# v5.net
KiCad netlist of a schematic drawn in EAGLE
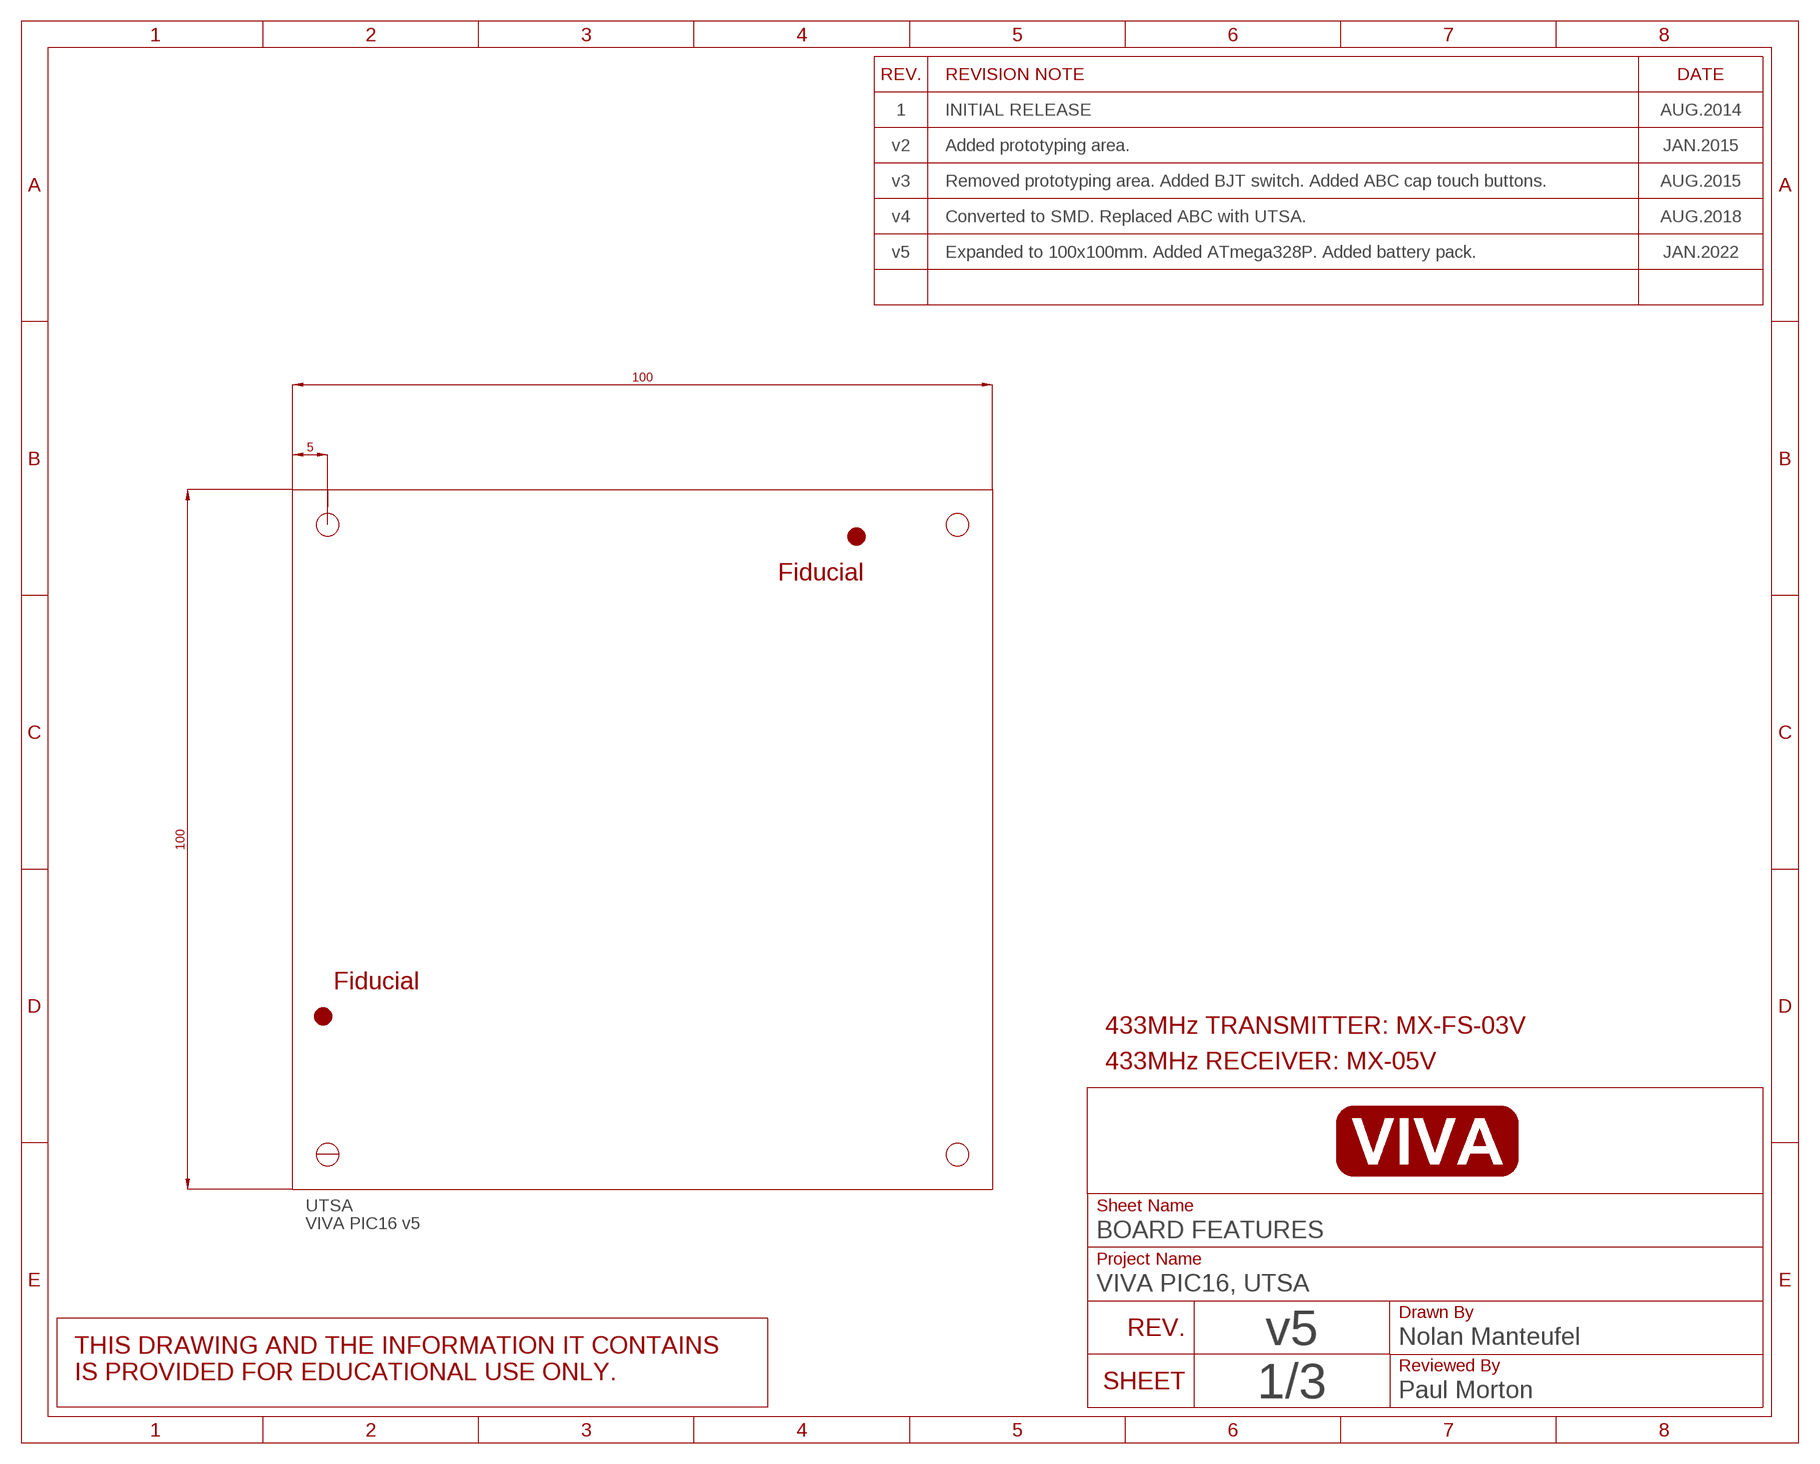
[diagram p0: schematic, sheet 1]
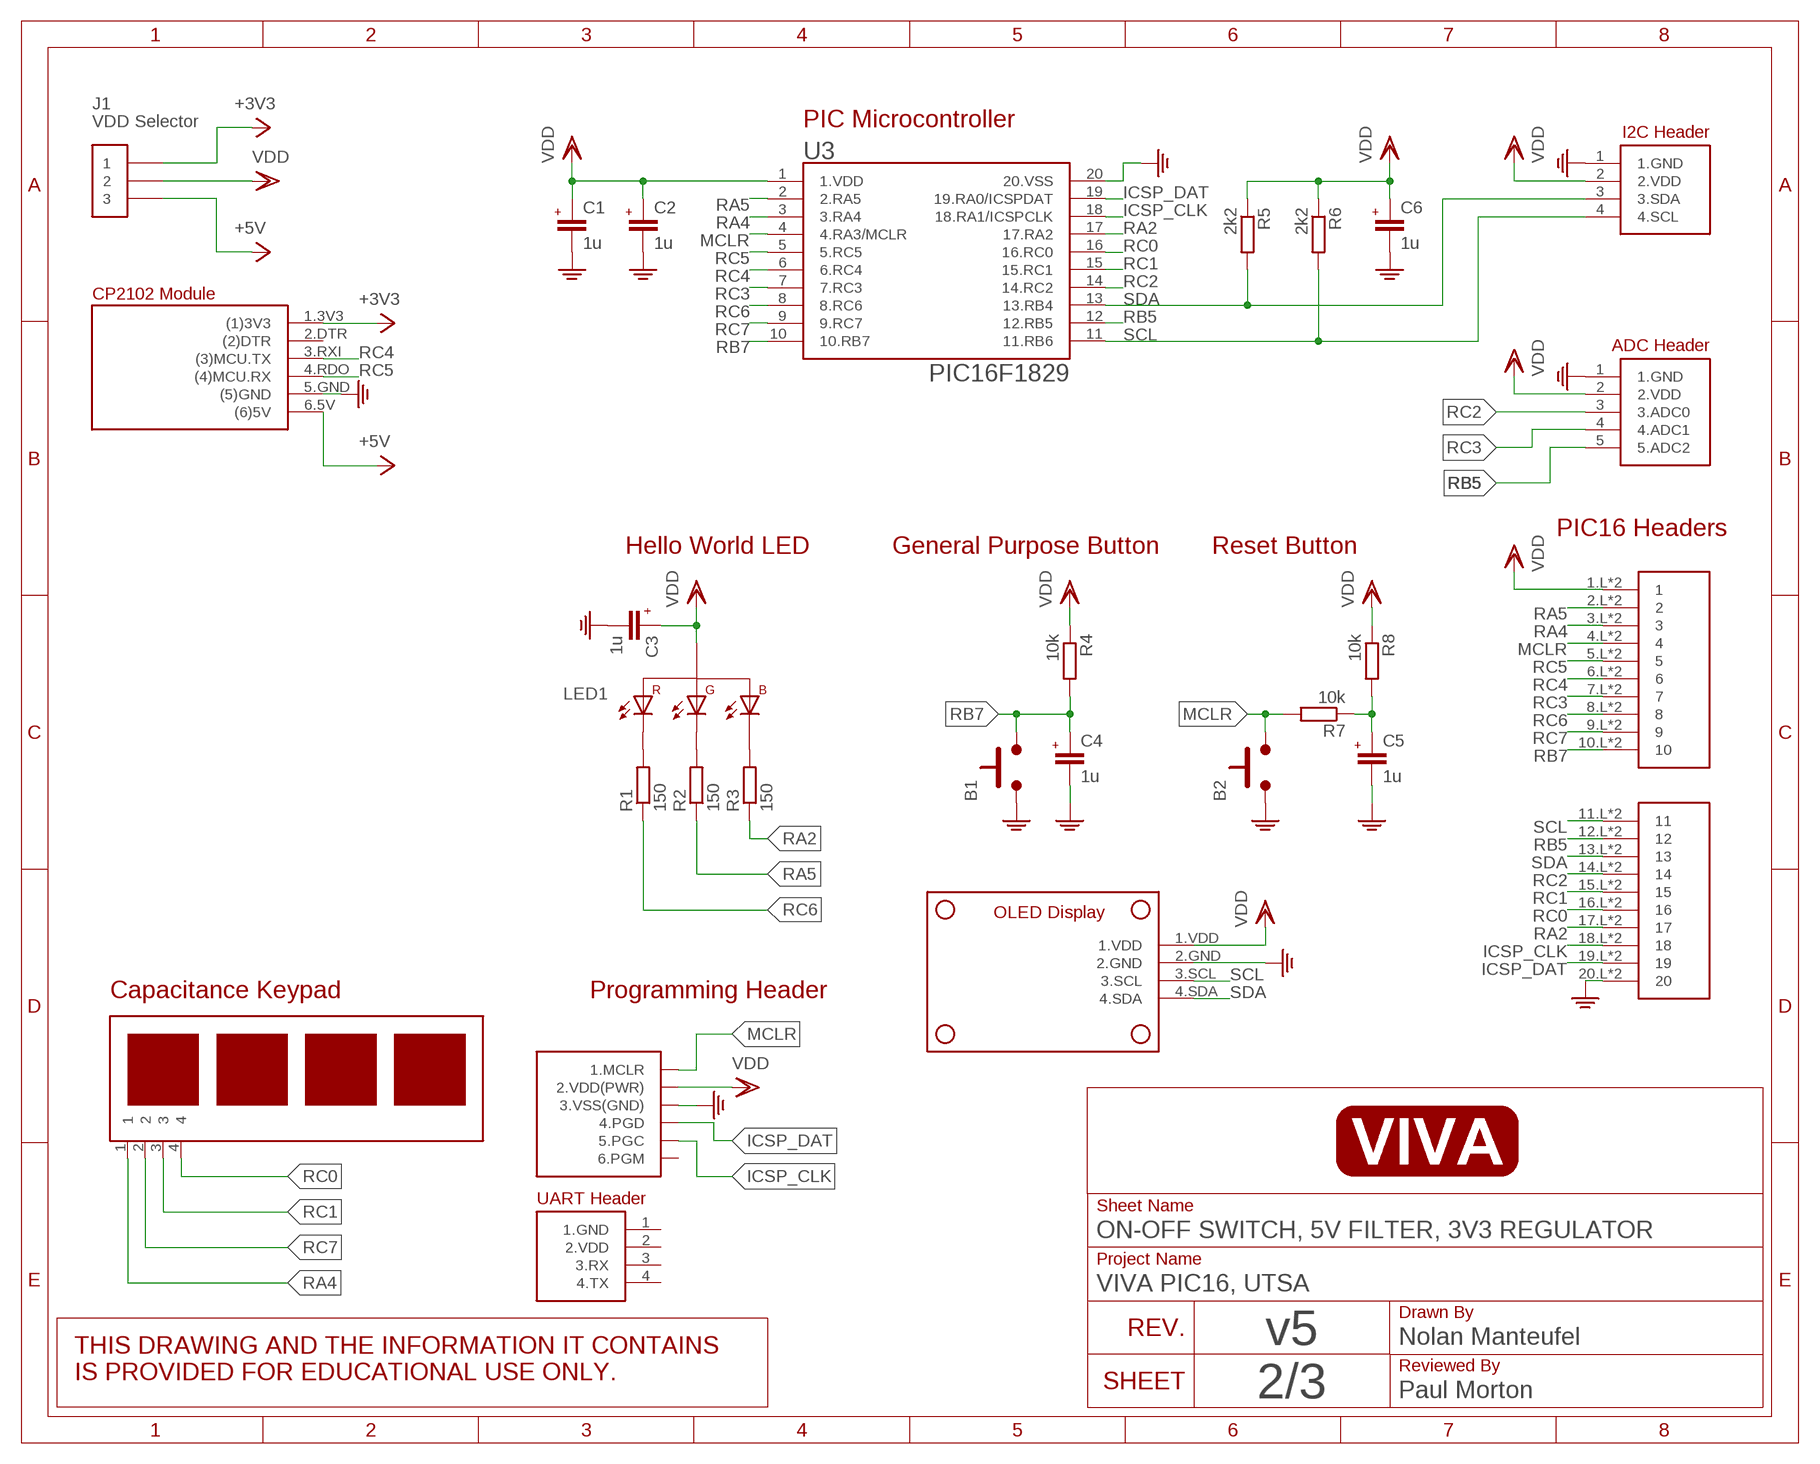
[diagram p1: schematic, sheet 2]
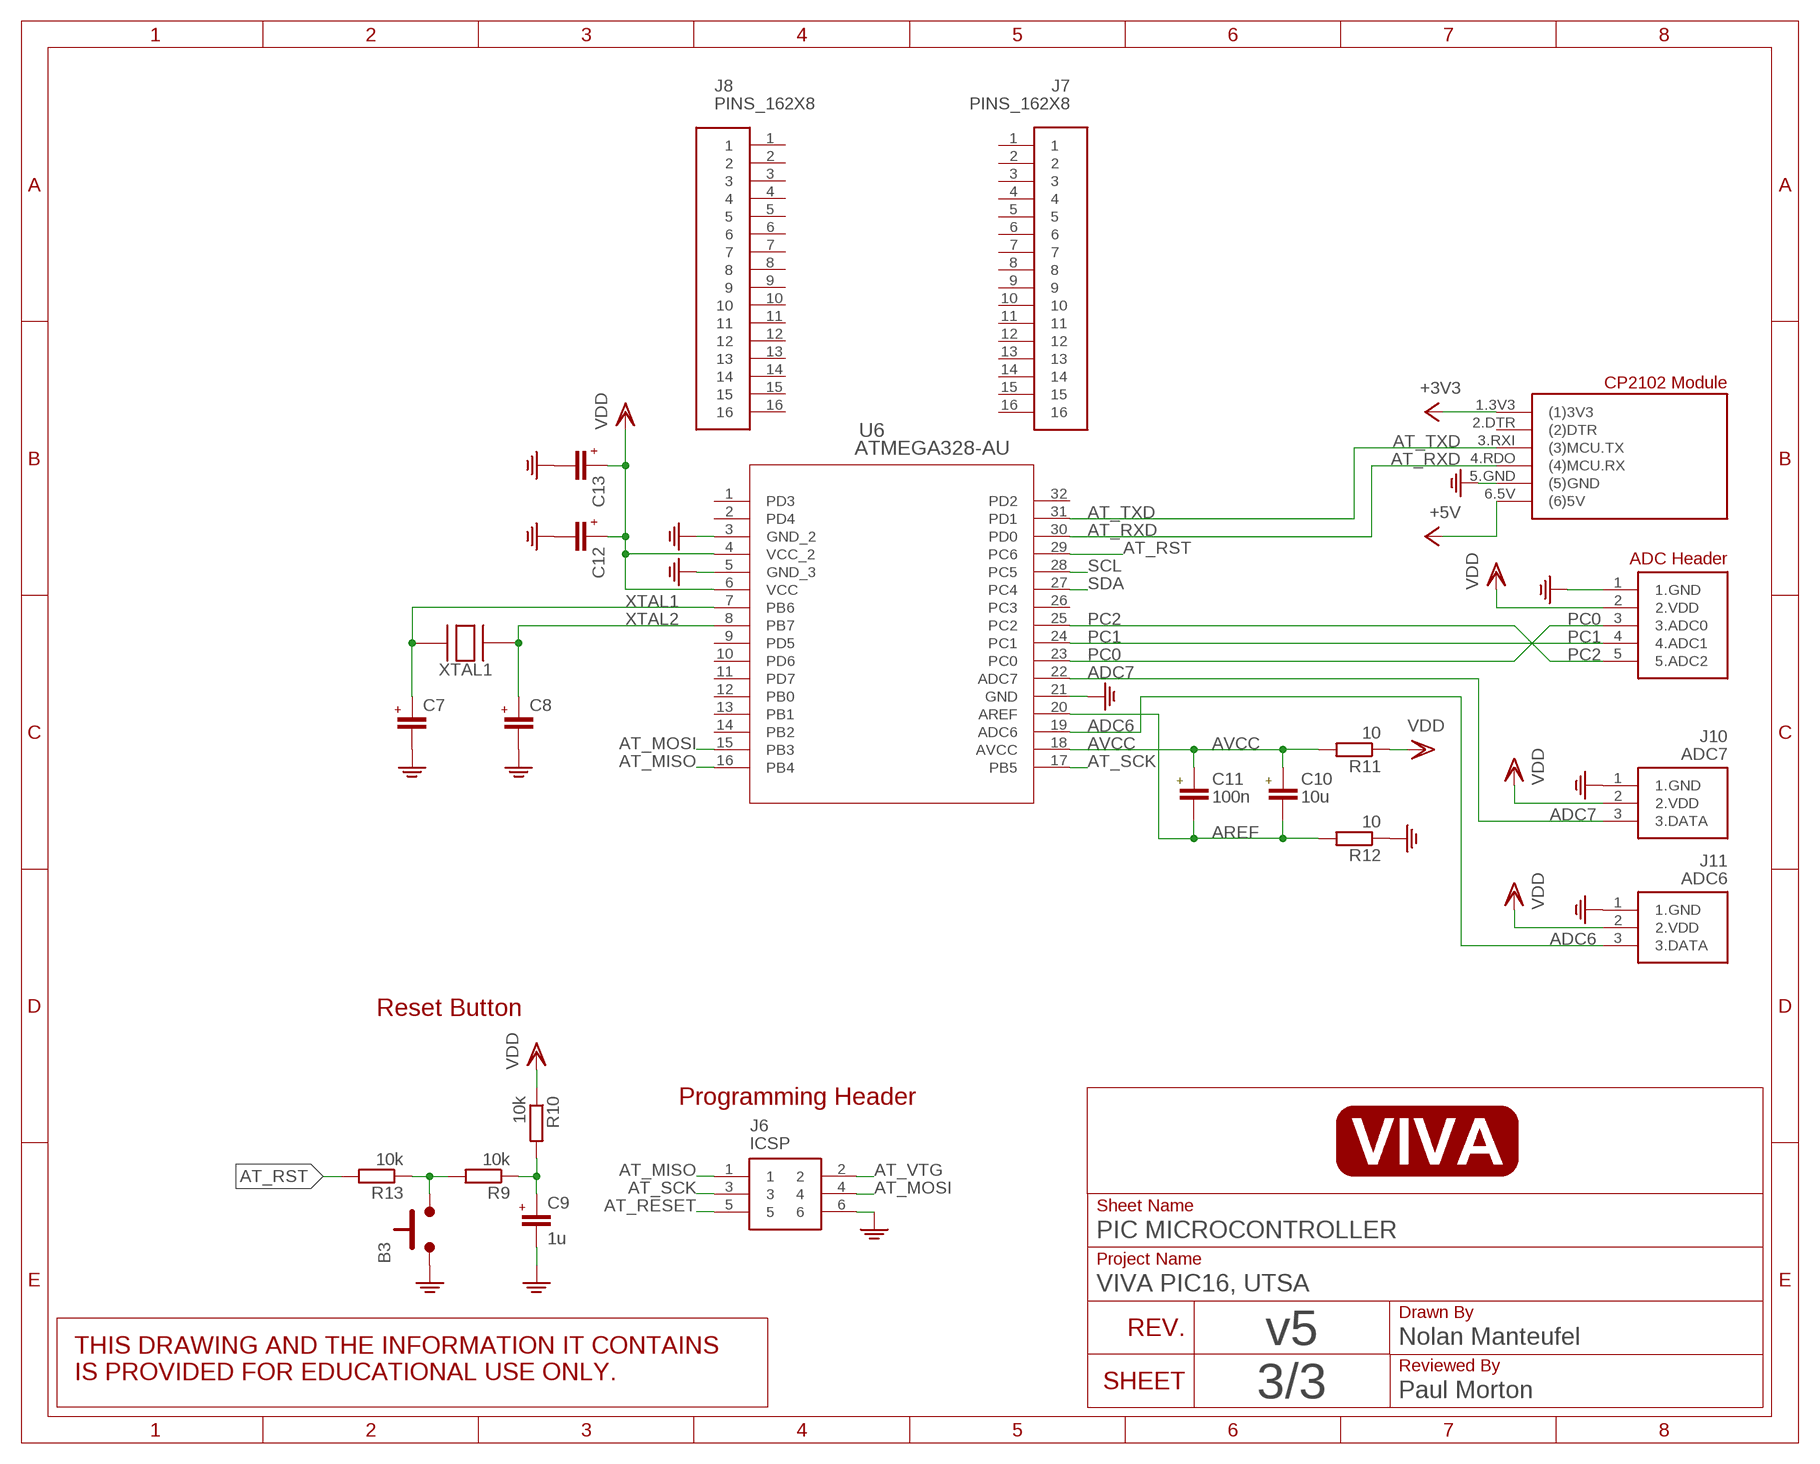
[diagram p2: schematic, sheet 3]

(export (version "E")
  (design (tool "Eeschema 10.0.6"))
  (components
    (comp (ref "B3")
      (value "PUSHBUTTON6X6MM")
      (footprint "eagle-import:6X6MM")
      (libsource (lib "eagle-import") (part "PUSHBUTTON6X6MM"))
    )
    (comp (ref "C7")
      (value "C0805")
      (footprint "eagle-import:C0805")
      (libsource (lib "eagle-import") (part "C0805"))
    )
    (comp (ref "C8")
      (value "C0805")
      (footprint "eagle-import:C0805")
      (libsource (lib "eagle-import") (part "C0805"))
    )
    (comp (ref "C9")
      (value "1u")
      (footprint "eagle-import:C0805")
      (libsource (lib "eagle-import") (part "C0805"))
    )
    (comp (ref "C10")
      (value "10u")
      (footprint "eagle-import:C0805")
      (libsource (lib "eagle-import") (part "C-EU_C0805"))
    )
    (comp (ref "C11")
      (value "100n")
      (footprint "eagle-import:C0805")
      (libsource (lib "eagle-import") (part "C-EU_C0805"))
    )
    (comp (ref "C12")
      (value "C0805")
      (footprint "eagle-import:C0805")
      (libsource (lib "eagle-import") (part "C0805"))
    )
    (comp (ref "C13")
      (value "C0805")
      (footprint "eagle-import:C0805")
      (libsource (lib "eagle-import") (part "C0805"))
    )
    (comp (ref "J6")
      (value "ICSP")
      (footprint "eagle-import:PINS_6-2X3")
      (libsource (lib "eagle-import") (part "PINS_6-2X3"))
    )
    (comp (ref "J7")
      (value "PINS_162X8")
      (footprint "eagle-import:PINS16_2X8")
      (libsource (lib "eagle-import") (part "PINS_162X8"))
    )
    (comp (ref "J8")
      (value "PINS_162X8")
      (footprint "eagle-import:PINS16_2X8")
      (libsource (lib "eagle-import") (part "PINS_162X8"))
    )
    (comp (ref "J9")
      (value "VIVA-HEADER-ADC-PIC16")
      (footprint "eagle-import:VIVA-HEADER-ADC-PIC16")
      (libsource (lib "eagle-import") (part "VIVA-HEADER-ADC-PIC16"))
    )
    (comp (ref "J10")
      (value "ADC7")
      (footprint "eagle-import:VIVA-HEADER-GPIO-RA-1")
      (libsource (lib "eagle-import") (part "VIVA-HEADER-GPIO-1"))
    )
    (comp (ref "J11")
      (value "ADC6")
      (footprint "eagle-import:VIVA-HEADER-GPIO-RA-1")
      (libsource (lib "eagle-import") (part "VIVA-HEADER-GPIO-1"))
    )
    (comp (ref "R9")
      (value "10k")
      (footprint "eagle-import:R0805")
      (libsource (lib "eagle-import") (part "R-EU__R0805"))
    )
    (comp (ref "R10")
      (value "10k")
      (footprint "eagle-import:R0805")
      (libsource (lib "eagle-import") (part "R-EU__R0805"))
    )
    (comp (ref "R11")
      (value "10")
      (footprint "eagle-import:R0805")
      (libsource (lib "eagle-import") (part "R-EU__R0805"))
    )
    (comp (ref "R12")
      (value "10")
      (footprint "eagle-import:R0805")
      (libsource (lib "eagle-import") (part "R-EU__R0805"))
    )
    (comp (ref "R13")
      (value "10k")
      (footprint "eagle-import:R0805")
      (libsource (lib "eagle-import") (part "R-EU__R0805"))
    )
    (comp (ref "U6")
      (value "ATMEGA328-AU")
      (footprint "eagle-import:32A_ATM")
      (fields (field (name "COPYRIGHT") "Copyright (C) 2021 Ultra Librarian. All rights reserved."))
      (libsource (lib "eagle-import") (part "ATMEGA328-AU"))
    )
    (comp (ref "U7")
      (value "VIVA_USB-TTL")
      (footprint "eagle-import:VIVA_USB_TTL_SUBTEXT")
      (libsource (lib "eagle-import") (part "VIVA_USB-TTL"))
    )
    (comp (ref "XTAL1")
      (value "CRYSTAL-SMD")
      (footprint "eagle-import:HC49S-SMD")
      (libsource (lib "eagle-import") (part "CRYSTAL-SMD"))
    )
    (comp (ref "B1")
      (value "PUSHBUTTON6X6MM")
      (footprint "eagle-import:6X6MM")
      (libsource (lib "eagle-import") (part "PUSHBUTTON6X6MM"))
    )
    (comp (ref "B2")
      (value "PUSHBUTTON6X6MM")
      (footprint "eagle-import:6X6MM")
      (libsource (lib "eagle-import") (part "PUSHBUTTON6X6MM"))
    )
    (comp (ref "C1")
      (value "1u")
      (footprint "eagle-import:C0805")
      (libsource (lib "eagle-import") (part "C0805"))
    )
    (comp (ref "C2")
      (value "1u")
      (footprint "eagle-import:C0805")
      (libsource (lib "eagle-import") (part "C0805"))
    )
    (comp (ref "C3")
      (value "1u")
      (footprint "eagle-import:C0805")
      (libsource (lib "eagle-import") (part "C0805"))
    )
    (comp (ref "C4")
      (value "1u")
      (footprint "eagle-import:C0805")
      (libsource (lib "eagle-import") (part "C0805"))
    )
    (comp (ref "C5")
      (value "1u")
      (footprint "eagle-import:C0805")
      (libsource (lib "eagle-import") (part "C0805"))
    )
    (comp (ref "C6")
      (value "1u")
      (footprint "eagle-import:C0805")
      (libsource (lib "eagle-import") (part "C0805"))
    )
    (comp (ref "J1")
      (value "VDD Selector")
      (footprint "eagle-import:PINS_3")
      (libsource (lib "eagle-import") (part "PINS_3_2.54"))
    )
    (comp (ref "J4")
      (value "PICKIT3")
      (footprint "eagle-import:PICKIT3")
      (libsource (lib "eagle-import") (part "PICKIT3"))
    )
    (comp (ref "J5")
      (value "VIVA-HEADER-ADC-PIC16")
      (footprint "eagle-import:VIVA-HEADER-ADC-PIC16")
      (libsource (lib "eagle-import") (part "VIVA-HEADER-ADC-PIC16"))
    )
    (comp (ref "LED1")
      (value "LED_RGBLTST-C19FD1WT")
      (footprint "eagle-import:0805_RGB")
      (libsource (lib "eagle-import") (part "LED_RGBLTST-C19FD1WT"))
    )
    (comp (ref "R1")
      (value "150")
      (footprint "eagle-import:R0805")
      (libsource (lib "eagle-import") (part "R-EU__R0805"))
    )
    (comp (ref "R2")
      (value "150")
      (footprint "eagle-import:R0805")
      (libsource (lib "eagle-import") (part "R-EU__R0805"))
    )
    (comp (ref "R3")
      (value "150")
      (footprint "eagle-import:R0805")
      (libsource (lib "eagle-import") (part "R-EU__R0805"))
    )
    (comp (ref "R4")
      (value "10k")
      (footprint "eagle-import:R0805")
      (libsource (lib "eagle-import") (part "R-EU__R0805"))
    )
    (comp (ref "R5")
      (value "2k2")
      (footprint "eagle-import:R0805")
      (libsource (lib "eagle-import") (part "R-EU__R0805"))
    )
    (comp (ref "R6")
      (value "2k2")
      (footprint "eagle-import:R0805")
      (libsource (lib "eagle-import") (part "R-EU__R0805"))
    )
    (comp (ref "R7")
      (value "10k")
      (footprint "eagle-import:R0805")
      (libsource (lib "eagle-import") (part "R-EU__R0805"))
    )
    (comp (ref "R8")
      (value "10k")
      (footprint "eagle-import:R0805")
      (libsource (lib "eagle-import") (part "R-EU__R0805"))
    )
    (comp (ref "U$2")
      (value "VIVA-HEADER-UART-XS")
      (footprint "eagle-import:PINS_4")
      (libsource (lib "eagle-import") (part "VIVA-HEADER-UART-XS"))
    )
    (comp (ref "U$3")
      (value "VIVA_OLED")
      (footprint "eagle-import:VIVA_OLED-I2C")
      (libsource (lib "eagle-import") (part "VIVA_OLED"))
    )
    (comp (ref "U1")
      (value "VIVA_UTSA-KEYPADV5")
      (footprint "eagle-import:VIVA_UTSA-KEYPAD-V5")
      (libsource (lib "eagle-import") (part "VIVA_UTSA-KEYPADV5"))
    )
    (comp (ref "U2")
      (value "VIVA_USB-TTL")
      (footprint "eagle-import:VIVA_USB_TTL_SUBTEXT")
      (libsource (lib "eagle-import") (part "VIVA_USB-TTL"))
    )
    (comp (ref "U3")
      (value "PIC16F1829")
      (footprint "eagle-import:SOP20-NEW")
      (libsource (lib "eagle-import") (part "PIC16F1829300"))
    )
    (comp (ref "U4")
      (value "VIVA-HEADER-I2C-RA")
      (footprint "eagle-import:VIVA-HEADER-I2C-RA")
      (libsource (lib "eagle-import") (part "VIVA-HEADER-I2C-RA"))
    )
    (comp (ref "U5")
      (value "VIVA_PIC16BOARD")
      (footprint "eagle-import:VIVA_PIC16")
      (libsource (lib "eagle-import") (part "VIVA_PIC16BOARD"))
    )
    (comp (ref "FIDUCIAL1")
      (value "FIDUCIAL")
      (footprint "eagle-import:FIDUCIAL")
      (libsource (lib "eagle-import") (part "FIDUCIAL"))
    )
    (comp (ref "FIDUCIAL2")
      (value "FIDUCIAL")
      (footprint "eagle-import:FIDUCIAL")
      (libsource (lib "eagle-import") (part "FIDUCIAL"))
    )
    (comp (ref "UTSA")
      (value "VIVA PIC16 v5")
      (footprint "eagle-import:PCB_100X100")
      (libsource (lib "eagle-import") (part "PCB_100X100"))
    )
  )
  (nets
    (net (code "1") (name "+3V3") (class "Default")
      (node (ref "J1") (pin "1") (pinfunction "1_1") (pintype "bidirectional"))
      (node (ref "U2") (pin "1.3V3") (pinfunction "(1)3V3_1.3V3") (pintype "bidirectional"))
      (node (ref "U7") (pin "1.3V3") (pinfunction "(1)3V3_1.3V3") (pintype "bidirectional"))
    )
    (net (code "2") (name "+5V") (class "Default")
      (node (ref "J1") (pin "3") (pinfunction "3_3") (pintype "bidirectional"))
      (node (ref "U2") (pin "6.5V") (pinfunction "(6)5V_6.5V") (pintype "bidirectional"))
      (node (ref "U7") (pin "6.5V") (pinfunction "(6)5V_6.5V") (pintype "bidirectional"))
    )
    (net (code "3") (name "ADC6") (class "Default")
      (node (ref "J11") (pin "3") (pinfunction "3.DATA_3") (pintype "bidirectional"))
      (node (ref "U6") (pin "19") (pinfunction "ADC6_19") (pintype "passive"))
    )
    (net (code "4") (name "ADC7") (class "Default")
      (node (ref "J10") (pin "3") (pinfunction "3.DATA_3") (pintype "bidirectional"))
      (node (ref "U6") (pin "22") (pinfunction "ADC7_22") (pintype "passive"))
    )
    (net (code "5") (name "AREF") (class "Default")
      (node (ref "C10") (pin "2") (pinfunction "2_2") (pintype "passive"))
      (node (ref "C11") (pin "2") (pinfunction "2_2") (pintype "passive"))
      (node (ref "R12") (pin "2") (pinfunction "2_2") (pintype "passive"))
      (node (ref "U6") (pin "20") (pinfunction "AREF_20") (pintype "passive"))
    )
    (net (code "6") (name "AT_MISO") (class "Default")
      (node (ref "J6") (pin "1") (pinfunction "1_1") (pintype "bidirectional"))
      (node (ref "U6") (pin "16") (pinfunction "PB4_16") (pintype "bidirectional"))
    )
    (net (code "7") (name "AT_MOSI") (class "Default")
      (node (ref "J6") (pin "4") (pinfunction "4_4") (pintype "bidirectional"))
      (node (ref "U6") (pin "15") (pinfunction "PB3_15") (pintype "bidirectional"))
    )
    (net (code "8") (name "AT_RESET") (class "Default")
      (node (ref "J6") (pin "5") (pinfunction "5_5") (pintype "bidirectional"))
    )
    (net (code "9") (name "AT_RST") (class "Default")
      (node (ref "R13") (pin "2") (pinfunction "2_2") (pintype "passive"))
      (node (ref "U6") (pin "29") (pinfunction "PC6_29") (pintype "bidirectional"))
    )
    (net (code "10") (name "AT_RXD") (class "Default")
      (node (ref "U6") (pin "30") (pinfunction "PD0_30") (pintype "bidirectional"))
      (node (ref "U7") (pin "4.RDO") (pinfunction "(4)MCU.RX_4.RDO") (pintype "bidirectional"))
    )
    (net (code "11") (name "AT_SCK") (class "Default")
      (node (ref "J6") (pin "3") (pinfunction "3_3") (pintype "bidirectional"))
      (node (ref "U6") (pin "17") (pinfunction "PB5_17") (pintype "bidirectional"))
    )
    (net (code "12") (name "AT_TXD") (class "Default")
      (node (ref "U6") (pin "31") (pinfunction "PD1_31") (pintype "bidirectional"))
      (node (ref "U7") (pin "3.RXI") (pinfunction "(3)MCU.TX_3.RXI") (pintype "bidirectional"))
    )
    (net (code "13") (name "AT_VTG") (class "Default")
      (node (ref "J6") (pin "2") (pinfunction "2_2") (pintype "bidirectional"))
    )
    (net (code "14") (name "AVCC") (class "Default")
      (node (ref "C10") (pin "1") (pinfunction "1_1") (pintype "passive"))
      (node (ref "C11") (pin "1") (pinfunction "1_1") (pintype "passive"))
      (node (ref "R11") (pin "2") (pinfunction "2_2") (pintype "passive"))
      (node (ref "U6") (pin "18") (pinfunction "AVCC_18") (pintype "power_in"))
    )
    (net (code "15") (name "GND") (class "Default")
      (node (ref "B1") (pin "1.A") (pinfunction "1_1.A") (pintype "bidirectional"))
      (node (ref "B1") (pin "2.A") (pinfunction "1_2.A") (pintype "bidirectional"))
      (node (ref "B2") (pin "1.A") (pinfunction "1_1.A") (pintype "bidirectional"))
      (node (ref "B2") (pin "2.A") (pinfunction "1_2.A") (pintype "bidirectional"))
      (node (ref "B3") (pin "1.A") (pinfunction "1_1.A") (pintype "bidirectional"))
      (node (ref "B3") (pin "2.A") (pinfunction "1_2.A") (pintype "bidirectional"))
      (node (ref "C1") (pin "1") (pinfunction "-_1") (pintype "passive"))
      (node (ref "C12") (pin "1") (pinfunction "-_1") (pintype "passive"))
      (node (ref "C13") (pin "1") (pinfunction "-_1") (pintype "passive"))
      (node (ref "C2") (pin "1") (pinfunction "-_1") (pintype "passive"))
      (node (ref "C3") (pin "1") (pinfunction "-_1") (pintype "passive"))
      (node (ref "C4") (pin "1") (pinfunction "-_1") (pintype "passive"))
      (node (ref "C5") (pin "1") (pinfunction "-_1") (pintype "passive"))
      (node (ref "C6") (pin "1") (pinfunction "-_1") (pintype "passive"))
      (node (ref "C7") (pin "1") (pinfunction "-_1") (pintype "passive"))
      (node (ref "C8") (pin "1") (pinfunction "-_1") (pintype "passive"))
      (node (ref "C9") (pin "1") (pinfunction "-_1") (pintype "passive"))
      (node (ref "J10") (pin "1") (pinfunction "1.GND_1") (pintype "bidirectional"))
      (node (ref "J11") (pin "1") (pinfunction "1.GND_1") (pintype "bidirectional"))
      (node (ref "J4") (pin "3") (pinfunction "3.VSS(GND)_3") (pintype "bidirectional"))
      (node (ref "J5") (pin "1") (pinfunction "1.GND_1") (pintype "bidirectional"))
      (node (ref "J6") (pin "6") (pinfunction "6_6") (pintype "bidirectional"))
      (node (ref "J9") (pin "1") (pinfunction "1.GND_1") (pintype "bidirectional"))
      (node (ref "R12") (pin "1") (pinfunction "1_1") (pintype "passive"))
      (node (ref "U$3") (pin "2.GND") (pinfunction "2.GND_2.GND") (pintype "bidirectional"))
      (node (ref "U2") (pin "5.GND") (pinfunction "(5)GND_5.GND") (pintype "bidirectional"))
      (node (ref "U3") (pin "20") (pinfunction "20.VSS_20") (pintype "bidirectional"))
      (node (ref "U4") (pin "1") (pinfunction "1.GND_1") (pintype "bidirectional"))
      (node (ref "U5") (pin "20.L") (pinfunction "20_20.L") (pintype "bidirectional"))
      (node (ref "U5") (pin "20.R") (pinfunction "20_20.R") (pintype "bidirectional"))
      (node (ref "U6") (pin "21") (pinfunction "GND_21") (pintype "power_in"))
      (node (ref "U6") (pin "3") (pinfunction "GND_2_3") (pintype "power_in"))
      (node (ref "U6") (pin "5") (pinfunction "GND_3_5") (pintype "power_in"))
      (node (ref "U7") (pin "5.GND") (pinfunction "(5)GND_5.GND") (pintype "bidirectional"))
    )
    (net (code "16") (name "ICSP_CLK") (class "Default")
      (node (ref "J4") (pin "5") (pinfunction "5.PGC_5") (pintype "bidirectional"))
      (node (ref "U3") (pin "18") (pinfunction "18.RA1/ICSPCLK_18") (pintype "bidirectional"))
      (node (ref "U5") (pin "18.L") (pinfunction "18_18.L") (pintype "bidirectional"))
      (node (ref "U5") (pin "18.R") (pinfunction "18_18.R") (pintype "bidirectional"))
    )
    (net (code "17") (name "ICSP_DAT") (class "Default")
      (node (ref "J4") (pin "4") (pinfunction "4.PGD_4") (pintype "bidirectional"))
      (node (ref "U3") (pin "19") (pinfunction "19.RA0/ICSPDAT_19") (pintype "bidirectional"))
      (node (ref "U5") (pin "19.L") (pinfunction "19_19.L") (pintype "bidirectional"))
      (node (ref "U5") (pin "19.R") (pinfunction "19_19.R") (pintype "bidirectional"))
    )
    (net (code "18") (name "MCLR") (class "Default")
      (node (ref "B2") (pin "3.B") (pinfunction "2_3.B") (pintype "bidirectional"))
      (node (ref "B2") (pin "4.B") (pinfunction "2_4.B") (pintype "bidirectional"))
      (node (ref "J4") (pin "1") (pinfunction "1.MCLR_1") (pintype "bidirectional"))
      (node (ref "R7") (pin "2") (pinfunction "2_2") (pintype "passive"))
      (node (ref "U3") (pin "4") (pinfunction "4.RA3/MCLR_4") (pintype "bidirectional"))
      (node (ref "U5") (pin "4.L") (pinfunction "4_4.L") (pintype "bidirectional"))
      (node (ref "U5") (pin "4.R") (pinfunction "4_4.R") (pintype "bidirectional"))
    )
    (net (code "19") (name "Net-(B3-2-Pad3.B)") (class "Default")
      (node (ref "B3") (pin "3.B") (pinfunction "2_3.B") (pintype "bidirectional"))
      (node (ref "B3") (pin "4.B") (pinfunction "2_4.B") (pintype "bidirectional"))
      (node (ref "R13") (pin "1") (pinfunction "1_1") (pintype "passive"))
      (node (ref "R9") (pin "2") (pinfunction "2_2") (pintype "passive"))
    )
    (net (code "20") (name "Net-(C5-+)") (class "Default")
      (node (ref "C5") (pin "2") (pinfunction "+_2") (pintype "passive"))
      (node (ref "R7") (pin "1") (pinfunction "1_1") (pintype "passive"))
      (node (ref "R8") (pin "2") (pinfunction "2_2") (pintype "passive"))
    )
    (net (code "21") (name "Net-(C9-+)") (class "Default")
      (node (ref "C9") (pin "2") (pinfunction "+_2") (pintype "passive"))
      (node (ref "R10") (pin "2") (pinfunction "2_2") (pintype "passive"))
      (node (ref "R9") (pin "1") (pinfunction "1_1") (pintype "passive"))
    )
    (net (code "22") (name "Net-(LED1-1.R-)") (class "Default")
      (node (ref "LED1") (pin "2") (pinfunction "1.R-_2") (pintype "passive"))
      (node (ref "R1") (pin "2") (pinfunction "2_2") (pintype "passive"))
    )
    (net (code "23") (name "Net-(LED1-2.G-)") (class "Default")
      (node (ref "LED1") (pin "3") (pinfunction "2.G-_3") (pintype "passive"))
      (node (ref "R2") (pin "2") (pinfunction "2_2") (pintype "passive"))
    )
    (net (code "24") (name "Net-(LED1-4.B-)") (class "Default")
      (node (ref "LED1") (pin "1") (pinfunction "4.B-_1") (pintype "passive"))
      (node (ref "R3") (pin "2") (pinfunction "2_2") (pintype "passive"))
    )
    (net (code "25") (name "PC0") (class "Default")
      (node (ref "J9") (pin "3") (pinfunction "3.ADC0_3") (pintype "bidirectional"))
      (node (ref "U6") (pin "23") (pinfunction "PC0_23") (pintype "bidirectional"))
    )
    (net (code "26") (name "PC1") (class "Default")
      (node (ref "J9") (pin "4") (pinfunction "4.ADC1_4") (pintype "bidirectional"))
      (node (ref "U6") (pin "24") (pinfunction "PC1_24") (pintype "bidirectional"))
    )
    (net (code "27") (name "PC2") (class "Default")
      (node (ref "J9") (pin "5") (pinfunction "5.ADC2_5") (pintype "bidirectional"))
      (node (ref "U6") (pin "25") (pinfunction "PC2_25") (pintype "bidirectional"))
    )
    (net (code "28") (name "RA2") (class "Default")
      (node (ref "R3") (pin "1") (pinfunction "1_1") (pintype "passive"))
      (node (ref "U3") (pin "17") (pinfunction "17.RA2_17") (pintype "bidirectional"))
      (node (ref "U5") (pin "17.L") (pinfunction "17_17.L") (pintype "bidirectional"))
      (node (ref "U5") (pin "17.R") (pinfunction "17_17.R") (pintype "bidirectional"))
    )
    (net (code "29") (name "RA4") (class "Default")
      (node (ref "U1") (pin "1") (pinfunction "1_1") (pintype "bidirectional"))
      (node (ref "U3") (pin "3") (pinfunction "3.RA4_3") (pintype "bidirectional"))
      (node (ref "U5") (pin "3.L") (pinfunction "3_3.L") (pintype "bidirectional"))
      (node (ref "U5") (pin "3.R") (pinfunction "3_3.R") (pintype "bidirectional"))
    )
    (net (code "30") (name "RA5") (class "Default")
      (node (ref "R2") (pin "1") (pinfunction "1_1") (pintype "passive"))
      (node (ref "U3") (pin "2") (pinfunction "2.RA5_2") (pintype "bidirectional"))
      (node (ref "U5") (pin "2.L") (pinfunction "2_2.L") (pintype "bidirectional"))
      (node (ref "U5") (pin "2.R") (pinfunction "2_2.R") (pintype "bidirectional"))
    )
    (net (code "31") (name "RB5") (class "Default")
      (node (ref "J5") (pin "5") (pinfunction "5.ADC2_5") (pintype "bidirectional"))
      (node (ref "U3") (pin "12") (pinfunction "12.RB5_12") (pintype "bidirectional"))
      (node (ref "U5") (pin "12.L") (pinfunction "12_12.L") (pintype "bidirectional"))
      (node (ref "U5") (pin "12.R") (pinfunction "12_12.R") (pintype "bidirectional"))
    )
    (net (code "32") (name "RB7") (class "Default")
      (node (ref "B1") (pin "3.B") (pinfunction "2_3.B") (pintype "bidirectional"))
      (node (ref "B1") (pin "4.B") (pinfunction "2_4.B") (pintype "bidirectional"))
      (node (ref "C4") (pin "2") (pinfunction "+_2") (pintype "passive"))
      (node (ref "R4") (pin "2") (pinfunction "2_2") (pintype "passive"))
      (node (ref "U3") (pin "10") (pinfunction "10.RB7_10") (pintype "bidirectional"))
      (node (ref "U5") (pin "10.L") (pinfunction "10_10.L") (pintype "bidirectional"))
      (node (ref "U5") (pin "10.R") (pinfunction "10_10.R") (pintype "bidirectional"))
    )
    (net (code "33") (name "RC0") (class "Default")
      (node (ref "U1") (pin "4") (pinfunction "4_4") (pintype "bidirectional"))
      (node (ref "U3") (pin "16") (pinfunction "16.RC0_16") (pintype "bidirectional"))
      (node (ref "U5") (pin "16.L") (pinfunction "16_16.L") (pintype "bidirectional"))
      (node (ref "U5") (pin "16.R") (pinfunction "16_16.R") (pintype "bidirectional"))
    )
    (net (code "34") (name "RC1") (class "Default")
      (node (ref "U1") (pin "3") (pinfunction "3_3") (pintype "bidirectional"))
      (node (ref "U3") (pin "15") (pinfunction "15.RC1_15") (pintype "bidirectional"))
      (node (ref "U5") (pin "15.L") (pinfunction "15_15.L") (pintype "bidirectional"))
      (node (ref "U5") (pin "15.R") (pinfunction "15_15.R") (pintype "bidirectional"))
    )
    (net (code "35") (name "RC2") (class "Default")
      (node (ref "J5") (pin "3") (pinfunction "3.ADC0_3") (pintype "bidirectional"))
      (node (ref "U3") (pin "14") (pinfunction "14.RC2_14") (pintype "bidirectional"))
      (node (ref "U5") (pin "14.L") (pinfunction "14_14.L") (pintype "bidirectional"))
      (node (ref "U5") (pin "14.R") (pinfunction "14_14.R") (pintype "bidirectional"))
    )
    (net (code "36") (name "RC3") (class "Default")
      (node (ref "J5") (pin "4") (pinfunction "4.ADC1_4") (pintype "bidirectional"))
      (node (ref "U3") (pin "7") (pinfunction "7.RC3_7") (pintype "bidirectional"))
      (node (ref "U5") (pin "7.L") (pinfunction "7_7.L") (pintype "bidirectional"))
      (node (ref "U5") (pin "7.R") (pinfunction "7_7.R") (pintype "bidirectional"))
    )
    (net (code "37") (name "RC4") (class "Default")
      (node (ref "U2") (pin "3.RXI") (pinfunction "(3)MCU.TX_3.RXI") (pintype "bidirectional"))
      (node (ref "U3") (pin "6") (pinfunction "6.RC4_6") (pintype "bidirectional"))
      (node (ref "U5") (pin "6.L") (pinfunction "6_6.L") (pintype "bidirectional"))
      (node (ref "U5") (pin "6.R") (pinfunction "6_6.R") (pintype "bidirectional"))
    )
    (net (code "38") (name "RC5") (class "Default")
      (node (ref "U2") (pin "4.RDO") (pinfunction "(4)MCU.RX_4.RDO") (pintype "bidirectional"))
      (node (ref "U3") (pin "5") (pinfunction "5.RC5_5") (pintype "bidirectional"))
      (node (ref "U5") (pin "5.L") (pinfunction "5_5.L") (pintype "bidirectional"))
      (node (ref "U5") (pin "5.R") (pinfunction "5_5.R") (pintype "bidirectional"))
    )
    (net (code "39") (name "RC6") (class "Default")
      (node (ref "R1") (pin "1") (pinfunction "1_1") (pintype "passive"))
      (node (ref "U3") (pin "8") (pinfunction "8.RC6_8") (pintype "bidirectional"))
      (node (ref "U5") (pin "8.L") (pinfunction "8_8.L") (pintype "bidirectional"))
      (node (ref "U5") (pin "8.R") (pinfunction "8_8.R") (pintype "bidirectional"))
    )
    (net (code "40") (name "RC7") (class "Default")
      (node (ref "U1") (pin "2") (pinfunction "2_2") (pintype "bidirectional"))
      (node (ref "U3") (pin "9") (pinfunction "9.RC7_9") (pintype "bidirectional"))
      (node (ref "U5") (pin "9.L") (pinfunction "9_9.L") (pintype "bidirectional"))
      (node (ref "U5") (pin "9.R") (pinfunction "9_9.R") (pintype "bidirectional"))
    )
    (net (code "41") (name "SCL") (class "Default")
      (node (ref "R6") (pin "2") (pinfunction "2_2") (pintype "passive"))
      (node (ref "U$3") (pin "3.SCL") (pinfunction "3.SCL_3.SCL") (pintype "bidirectional"))
      (node (ref "U3") (pin "11") (pinfunction "11.RB6_11") (pintype "bidirectional"))
      (node (ref "U4") (pin "4") (pinfunction "4.SCL_4") (pintype "bidirectional"))
      (node (ref "U5") (pin "11.L") (pinfunction "11_11.L") (pintype "bidirectional"))
      (node (ref "U5") (pin "11.R") (pinfunction "11_11.R") (pintype "bidirectional"))
      (node (ref "U6") (pin "28") (pinfunction "PC5_28") (pintype "bidirectional"))
    )
    (net (code "42") (name "SDA") (class "Default")
      (node (ref "R5") (pin "2") (pinfunction "2_2") (pintype "passive"))
      (node (ref "U$3") (pin "4.SDA") (pinfunction "4.SDA_4.SDA") (pintype "bidirectional"))
      (node (ref "U3") (pin "13") (pinfunction "13.RB4_13") (pintype "bidirectional"))
      (node (ref "U4") (pin "3") (pinfunction "3.SDA_3") (pintype "bidirectional"))
      (node (ref "U5") (pin "13.L") (pinfunction "13_13.L") (pintype "bidirectional"))
      (node (ref "U5") (pin "13.R") (pinfunction "13_13.R") (pintype "bidirectional"))
      (node (ref "U6") (pin "27") (pinfunction "PC4_27") (pintype "bidirectional"))
    )
    (net (code "43") (name "VDD") (class "Default")
      (node (ref "C1") (pin "2") (pinfunction "+_2") (pintype "passive"))
      (node (ref "C12") (pin "2") (pinfunction "+_2") (pintype "passive"))
      (node (ref "C13") (pin "2") (pinfunction "+_2") (pintype "passive"))
      (node (ref "C2") (pin "2") (pinfunction "+_2") (pintype "passive"))
      (node (ref "C3") (pin "2") (pinfunction "+_2") (pintype "passive"))
      (node (ref "C6") (pin "2") (pinfunction "+_2") (pintype "passive"))
      (node (ref "J1") (pin "2") (pinfunction "2_2") (pintype "bidirectional"))
      (node (ref "J10") (pin "2") (pinfunction "2.VDD_2") (pintype "bidirectional"))
      (node (ref "J11") (pin "2") (pinfunction "2.VDD_2") (pintype "bidirectional"))
      (node (ref "J4") (pin "2") (pinfunction "2.VDD(PWR)_2") (pintype "bidirectional"))
      (node (ref "J5") (pin "2") (pinfunction "2.VDD_2") (pintype "bidirectional"))
      (node (ref "J9") (pin "2") (pinfunction "2.VDD_2") (pintype "bidirectional"))
      (node (ref "LED1") (pin "4") (pinfunction "3.+_4") (pintype "passive"))
      (node (ref "R10") (pin "1") (pinfunction "1_1") (pintype "passive"))
      (node (ref "R11") (pin "1") (pinfunction "1_1") (pintype "passive"))
      (node (ref "R4") (pin "1") (pinfunction "1_1") (pintype "passive"))
      (node (ref "R5") (pin "1") (pinfunction "1_1") (pintype "passive"))
      (node (ref "R6") (pin "1") (pinfunction "1_1") (pintype "passive"))
      (node (ref "R8") (pin "1") (pinfunction "1_1") (pintype "passive"))
      (node (ref "U$3") (pin "1.VDD") (pinfunction "1.VDD_1.VDD") (pintype "bidirectional"))
      (node (ref "U3") (pin "1") (pinfunction "1.VDD_1") (pintype "bidirectional"))
      (node (ref "U4") (pin "2") (pinfunction "2.VDD_2") (pintype "bidirectional"))
      (node (ref "U5") (pin "1.L") (pinfunction "1_1.L") (pintype "bidirectional"))
      (node (ref "U5") (pin "1.R") (pinfunction "1_1.R") (pintype "bidirectional"))
      (node (ref "U6") (pin "4") (pinfunction "VCC_2_4") (pintype "power_in"))
      (node (ref "U6") (pin "6") (pinfunction "VCC_6") (pintype "power_in"))
    )
    (net (code "44") (name "XTAL1") (class "Default")
      (node (ref "C7") (pin "2") (pinfunction "+_2") (pintype "passive"))
      (node (ref "U6") (pin "7") (pinfunction "PB6_7") (pintype "bidirectional"))
      (node (ref "XTAL1") (pin "2") (pinfunction "2_2") (pintype "bidirectional"))
      (node (ref "XTAL1") (pin "4") (pinfunction "2_4") (pintype "bidirectional"))
    )
    (net (code "45") (name "XTAL2") (class "Default")
      (node (ref "C8") (pin "2") (pinfunction "+_2") (pintype "passive"))
      (node (ref "U6") (pin "8") (pinfunction "PB7_8") (pintype "bidirectional"))
      (node (ref "XTAL1") (pin "1") (pinfunction "1_1") (pintype "bidirectional"))
      (node (ref "XTAL1") (pin "3") (pinfunction "1_3") (pintype "bidirectional"))
    )
    (net (code "46") (name "unconnected-(J4-6.PGM-Pad6)") (class "Default")
      (node (ref "J4") (pin "6") (pinfunction "6.PGM_6") (pintype "bidirectional"))
    )
    (net (code "47") (name "unconnected-(J7-Pad1)") (class "Default")
      (node (ref "J7") (pin "1") (pinfunction "1_1") (pintype "bidirectional"))
    )
    (net (code "48") (name "unconnected-(J7-Pad2)") (class "Default")
      (node (ref "J7") (pin "2") (pinfunction "2_2") (pintype "bidirectional"))
    )
    (net (code "49") (name "unconnected-(J7-Pad3)") (class "Default")
      (node (ref "J7") (pin "3") (pinfunction "3_3") (pintype "bidirectional"))
    )
    (net (code "50") (name "unconnected-(J7-Pad4)") (class "Default")
      (node (ref "J7") (pin "4") (pinfunction "4_4") (pintype "bidirectional"))
    )
    (net (code "51") (name "unconnected-(J7-Pad5)") (class "Default")
      (node (ref "J7") (pin "5") (pinfunction "5_5") (pintype "bidirectional"))
    )
    (net (code "52") (name "unconnected-(J7-Pad6)") (class "Default")
      (node (ref "J7") (pin "6") (pinfunction "6_6") (pintype "bidirectional"))
    )
    (net (code "53") (name "unconnected-(J7-Pad7)") (class "Default")
      (node (ref "J7") (pin "7") (pinfunction "7_7") (pintype "bidirectional"))
    )
    (net (code "54") (name "unconnected-(J7-Pad8)") (class "Default")
      (node (ref "J7") (pin "8") (pinfunction "8_8") (pintype "bidirectional"))
    )
    (net (code "55") (name "unconnected-(J7-Pad9)") (class "Default")
      (node (ref "J7") (pin "9") (pinfunction "9_9") (pintype "bidirectional"))
    )
    (net (code "56") (name "unconnected-(J7-Pad10)") (class "Default")
      (node (ref "J7") (pin "10") (pinfunction "10_10") (pintype "bidirectional"))
    )
    (net (code "57") (name "unconnected-(J7-Pad11)") (class "Default")
      (node (ref "J7") (pin "11") (pinfunction "11_11") (pintype "bidirectional"))
    )
    (net (code "58") (name "unconnected-(J7-Pad12)") (class "Default")
      (node (ref "J7") (pin "12") (pinfunction "12_12") (pintype "bidirectional"))
    )
    (net (code "59") (name "unconnected-(J7-Pad13)") (class "Default")
      (node (ref "J7") (pin "13") (pinfunction "13_13") (pintype "bidirectional"))
    )
    (net (code "60") (name "unconnected-(J7-Pad14)") (class "Default")
      (node (ref "J7") (pin "14") (pinfunction "14_14") (pintype "bidirectional"))
    )
    (net (code "61") (name "unconnected-(J7-Pad15)") (class "Default")
      (node (ref "J7") (pin "15") (pinfunction "15_15") (pintype "bidirectional"))
    )
    (net (code "62") (name "unconnected-(J7-Pad16)") (class "Default")
      (node (ref "J7") (pin "16") (pinfunction "16_16") (pintype "bidirectional"))
    )
    (net (code "63") (name "unconnected-(J8-Pad1)") (class "Default")
      (node (ref "J8") (pin "1") (pinfunction "1_1") (pintype "bidirectional"))
    )
    (net (code "64") (name "unconnected-(J8-Pad2)") (class "Default")
      (node (ref "J8") (pin "2") (pinfunction "2_2") (pintype "bidirectional"))
    )
    (net (code "65") (name "unconnected-(J8-Pad3)") (class "Default")
      (node (ref "J8") (pin "3") (pinfunction "3_3") (pintype "bidirectional"))
    )
    (net (code "66") (name "unconnected-(J8-Pad4)") (class "Default")
      (node (ref "J8") (pin "4") (pinfunction "4_4") (pintype "bidirectional"))
    )
    (net (code "67") (name "unconnected-(J8-Pad5)") (class "Default")
      (node (ref "J8") (pin "5") (pinfunction "5_5") (pintype "bidirectional"))
    )
    (net (code "68") (name "unconnected-(J8-Pad6)") (class "Default")
      (node (ref "J8") (pin "6") (pinfunction "6_6") (pintype "bidirectional"))
    )
    (net (code "69") (name "unconnected-(J8-Pad7)") (class "Default")
      (node (ref "J8") (pin "7") (pinfunction "7_7") (pintype "bidirectional"))
    )
    (net (code "70") (name "unconnected-(J8-Pad8)") (class "Default")
      (node (ref "J8") (pin "8") (pinfunction "8_8") (pintype "bidirectional"))
    )
    (net (code "71") (name "unconnected-(J8-Pad9)") (class "Default")
      (node (ref "J8") (pin "9") (pinfunction "9_9") (pintype "bidirectional"))
    )
    (net (code "72") (name "unconnected-(J8-Pad10)") (class "Default")
      (node (ref "J8") (pin "10") (pinfunction "10_10") (pintype "bidirectional"))
    )
    (net (code "73") (name "unconnected-(J8-Pad11)") (class "Default")
      (node (ref "J8") (pin "11") (pinfunction "11_11") (pintype "bidirectional"))
    )
    (net (code "74") (name "unconnected-(J8-Pad12)") (class "Default")
      (node (ref "J8") (pin "12") (pinfunction "12_12") (pintype "bidirectional"))
    )
    (net (code "75") (name "unconnected-(J8-Pad13)") (class "Default")
      (node (ref "J8") (pin "13") (pinfunction "13_13") (pintype "bidirectional"))
    )
    (net (code "76") (name "unconnected-(J8-Pad14)") (class "Default")
      (node (ref "J8") (pin "14") (pinfunction "14_14") (pintype "bidirectional"))
    )
    (net (code "77") (name "unconnected-(J8-Pad15)") (class "Default")
      (node (ref "J8") (pin "15") (pinfunction "15_15") (pintype "bidirectional"))
    )
    (net (code "78") (name "unconnected-(J8-Pad16)") (class "Default")
      (node (ref "J8") (pin "16") (pinfunction "16_16") (pintype "bidirectional"))
    )
    (net (code "79") (name "unconnected-(U$2-1.GND-Pad1)") (class "Default")
      (node (ref "U$2") (pin "1") (pinfunction "1.GND_1") (pintype "bidirectional"))
    )
    (net (code "80") (name "unconnected-(U$2-2.VDD-Pad2)") (class "Default")
      (node (ref "U$2") (pin "2") (pinfunction "2.VDD_2") (pintype "bidirectional"))
    )
    (net (code "81") (name "unconnected-(U$2-3.RX-Pad3)") (class "Default")
      (node (ref "U$2") (pin "3") (pinfunction "3.RX_3") (pintype "bidirectional"))
    )
    (net (code "82") (name "unconnected-(U$2-4.TX-Pad4)") (class "Default")
      (node (ref "U$2") (pin "4") (pinfunction "4.TX_4") (pintype "bidirectional"))
    )
    (net (code "83") (name "unconnected-(U2-(2)DTR-Pad2.DTR)") (class "Default")
      (node (ref "U2") (pin "2.DTR") (pinfunction "(2)DTR_2.DTR") (pintype "bidirectional"))
    )
    (net (code "84") (name "unconnected-(U6-PB0-Pad12)") (class "Default")
      (node (ref "U6") (pin "12") (pinfunction "PB0_12") (pintype "bidirectional"))
    )
    (net (code "85") (name "unconnected-(U6-PB1-Pad13)") (class "Default")
      (node (ref "U6") (pin "13") (pinfunction "PB1_13") (pintype "bidirectional"))
    )
    (net (code "86") (name "unconnected-(U6-PB2-Pad14)") (class "Default")
      (node (ref "U6") (pin "14") (pinfunction "PB2_14") (pintype "bidirectional"))
    )
    (net (code "87") (name "unconnected-(U6-PC3-Pad26)") (class "Default")
      (node (ref "U6") (pin "26") (pinfunction "PC3_26") (pintype "bidirectional"))
    )
    (net (code "88") (name "unconnected-(U6-PD2-Pad32)") (class "Default")
      (node (ref "U6") (pin "32") (pinfunction "PD2_32") (pintype "bidirectional"))
    )
    (net (code "89") (name "unconnected-(U6-PD3-Pad1)") (class "Default")
      (node (ref "U6") (pin "1") (pinfunction "PD3_1") (pintype "bidirectional"))
    )
    (net (code "90") (name "unconnected-(U6-PD4-Pad2)") (class "Default")
      (node (ref "U6") (pin "2") (pinfunction "PD4_2") (pintype "bidirectional"))
    )
    (net (code "91") (name "unconnected-(U6-PD5-Pad9)") (class "Default")
      (node (ref "U6") (pin "9") (pinfunction "PD5_9") (pintype "bidirectional"))
    )
    (net (code "92") (name "unconnected-(U6-PD6-Pad10)") (class "Default")
      (node (ref "U6") (pin "10") (pinfunction "PD6_10") (pintype "bidirectional"))
    )
    (net (code "93") (name "unconnected-(U6-PD7-Pad11)") (class "Default")
      (node (ref "U6") (pin "11") (pinfunction "PD7_11") (pintype "bidirectional"))
    )
    (net (code "94") (name "unconnected-(U7-(2)DTR-Pad2.DTR)") (class "Default")
      (node (ref "U7") (pin "2.DTR") (pinfunction "(2)DTR_2.DTR") (pintype "bidirectional"))
    )
  )
)
